# power_distributor.net
KiCad netlist of a schematic drawn in EAGLE
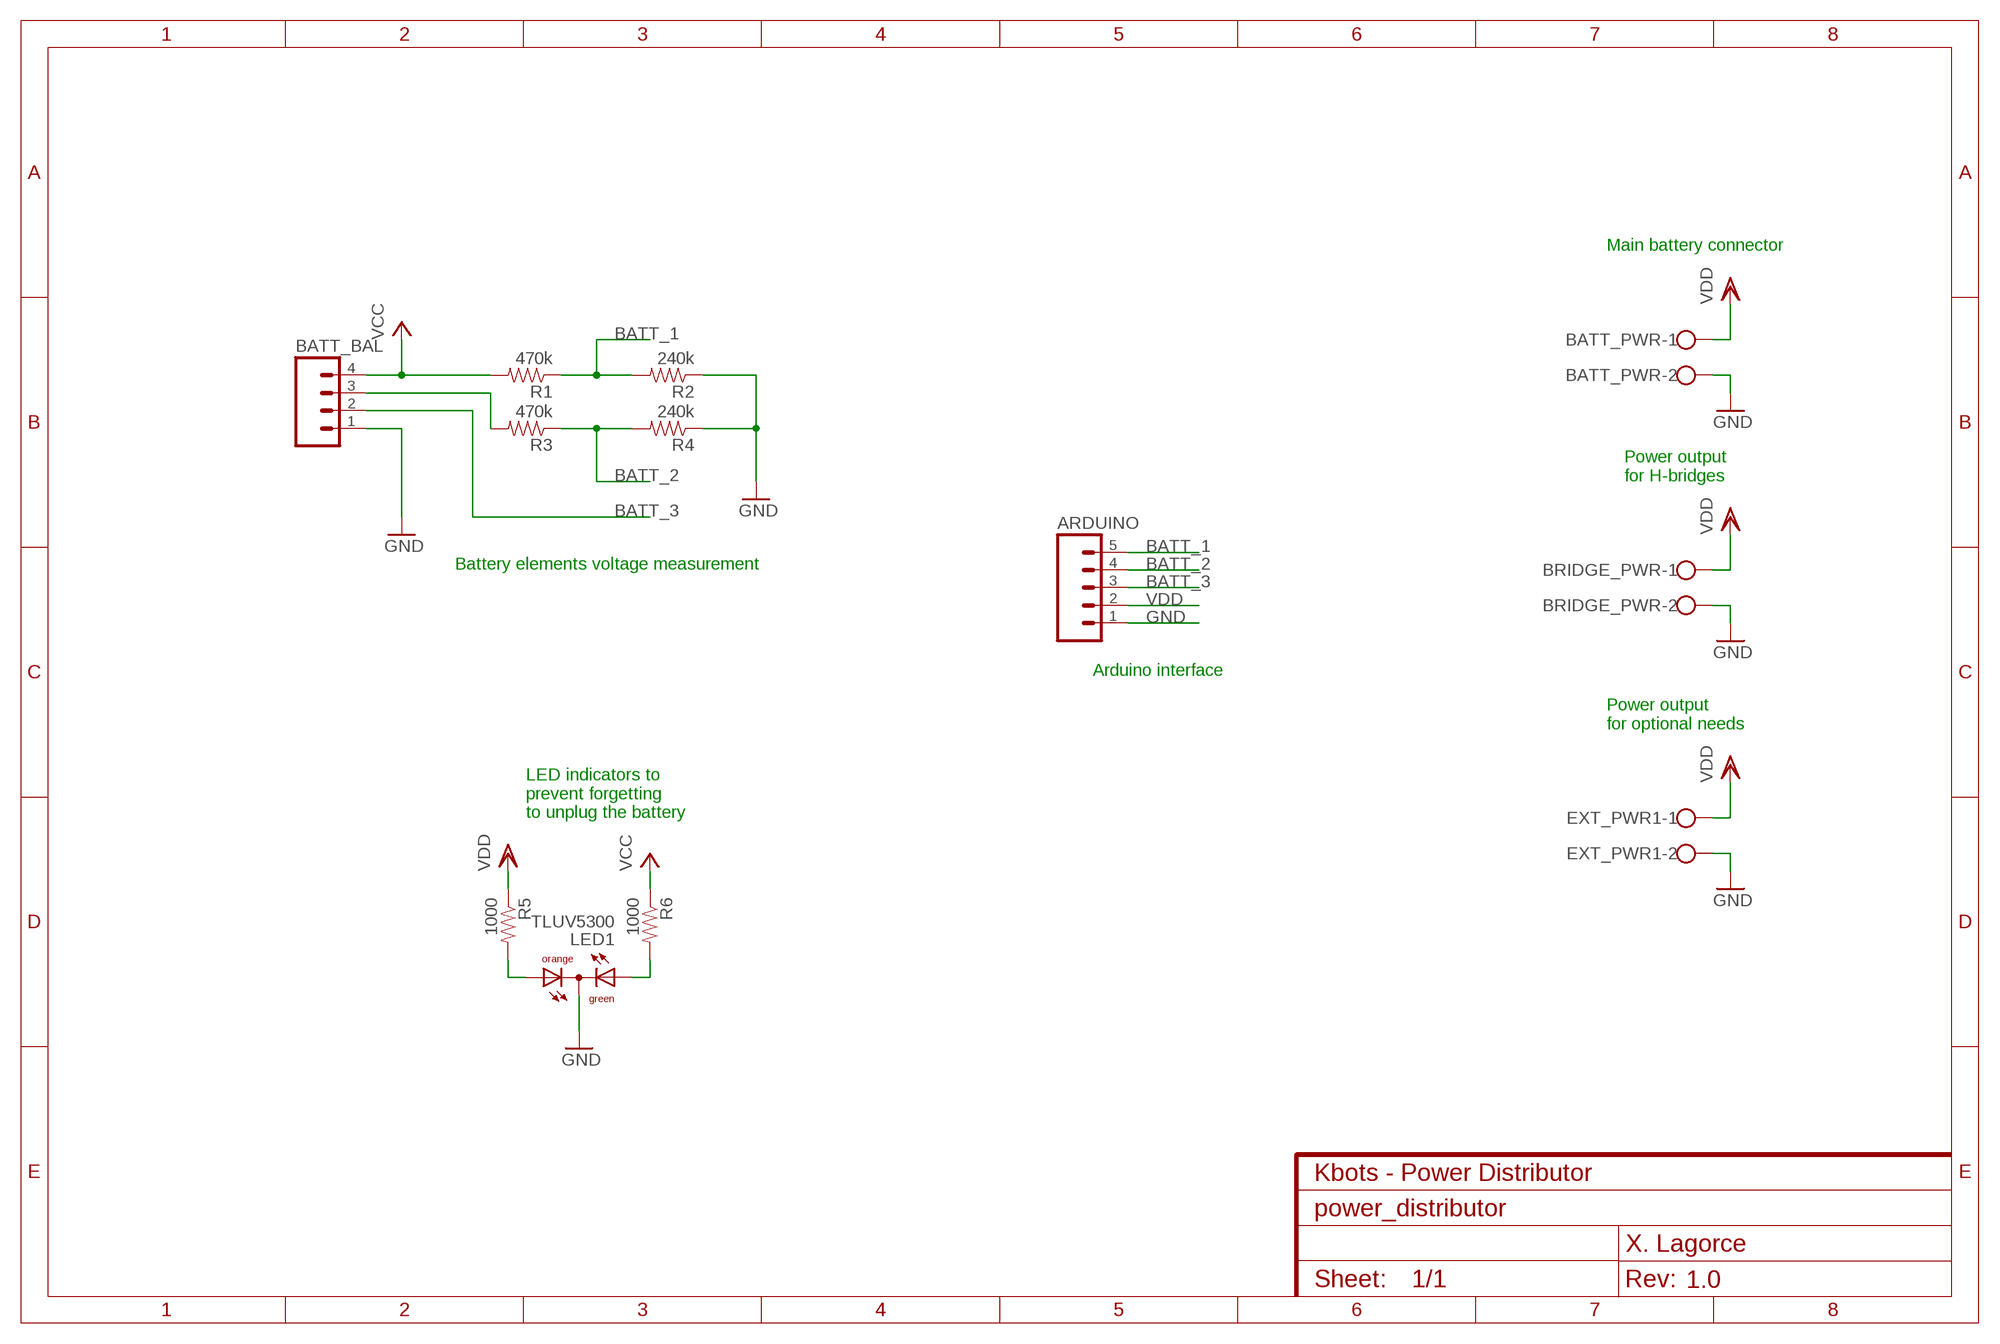
[diagram p0: schematic, sheet 1]

(export (version "E")
  (design (tool "Eeschema 10.0.6"))
  (components
    (comp (ref "ARDUINO")
      (value "M05PTH")
      (footprint "eagle-import:1X05")
      (libsource (lib "eagle-import") (part "M05PTH"))
    )
    (comp (ref "BATT_BAL")
      (value "M04POLAR")
      (footprint "eagle-import:MOLEX-1X4")
      (libsource (lib "eagle-import") (part "M04POLAR"))
    )
    (comp (ref "BATT_PWR")
      (value "W237-102")
      (footprint "eagle-import:W237-102")
      (fields (field (name "MPN") "237-102"))
      (libsource (lib "eagle-import") (part "W237-102"))
    )
    (comp (ref "BRIDGE_PWR")
      (value "W237-102")
      (footprint "eagle-import:W237-102")
      (fields (field (name "MPN") "237-102"))
      (libsource (lib "eagle-import") (part "W237-102"))
    )
    (comp (ref "EXT_PWR1")
      (value "W237-102")
      (footprint "eagle-import:W237-102")
      (fields (field (name "MPN") "237-102"))
      (libsource (lib "eagle-import") (part "W237-102"))
    )
    (comp (ref "LED1")
      (value "TLUV5300")
      (footprint "eagle-import:TLUV5300")
      (libsource (lib "eagle-import") (part "TLUV5300"))
    )
    (comp (ref "R1")
      (value "470k")
      (footprint "eagle-import:1206")
      (libsource (lib "eagle-import") (part "RESISTOR1206"))
    )
    (comp (ref "R2")
      (value "240k")
      (footprint "eagle-import:1206")
      (libsource (lib "eagle-import") (part "RESISTOR1206"))
    )
    (comp (ref "R3")
      (value "470k")
      (footprint "eagle-import:1206")
      (libsource (lib "eagle-import") (part "RESISTOR1206"))
    )
    (comp (ref "R4")
      (value "240k")
      (footprint "eagle-import:1206")
      (libsource (lib "eagle-import") (part "RESISTOR1206"))
    )
    (comp (ref "R5")
      (value "1000")
      (footprint "eagle-import:1206")
      (libsource (lib "eagle-import") (part "RESISTOR1206"))
    )
    (comp (ref "R6")
      (value "1000")
      (footprint "eagle-import:1206")
      (libsource (lib "eagle-import") (part "RESISTOR1206"))
    )
  )
  (nets
    (net (code "1") (name "/BATT_1") (class "Default")
      (node (ref "ARDUINO") (pin "5") (pinfunction "5_5") (pintype "passive"))
      (node (ref "R1") (pin "1") (pinfunction "1_1") (pintype "passive"))
      (node (ref "R2") (pin "2") (pinfunction "2_2") (pintype "passive"))
    )
    (net (code "2") (name "/BATT_2") (class "Default")
      (node (ref "ARDUINO") (pin "4") (pinfunction "4_4") (pintype "passive"))
      (node (ref "R3") (pin "1") (pinfunction "1_1") (pintype "passive"))
      (node (ref "R4") (pin "2") (pinfunction "2_2") (pintype "passive"))
    )
    (net (code "3") (name "/BATT_3") (class "Default")
      (node (ref "ARDUINO") (pin "3") (pinfunction "3_3") (pintype "passive"))
      (node (ref "BATT_BAL") (pin "2") (pinfunction "2_2") (pintype "passive"))
    )
    (net (code "4") (name "GND") (class "Default")
      (node (ref "ARDUINO") (pin "1") (pinfunction "1_1") (pintype "passive"))
      (node (ref "BATT_BAL") (pin "1") (pinfunction "1_1") (pintype "passive"))
      (node (ref "BATT_PWR") (pin "2") (pinfunction "KL_2") (pintype "passive"))
      (node (ref "BRIDGE_PWR") (pin "2") (pinfunction "KL_2") (pintype "passive"))
      (node (ref "EXT_PWR1") (pin "2") (pinfunction "KL_2") (pintype "passive"))
      (node (ref "LED1") (pin "CC") (pinfunction "CC_CC") (pintype "passive"))
      (node (ref "R2") (pin "1") (pinfunction "1_1") (pintype "passive"))
      (node (ref "R4") (pin "1") (pinfunction "1_1") (pintype "passive"))
    )
    (net (code "5") (name "Net-(BATT_BAL-Pad3)") (class "Default")
      (node (ref "BATT_BAL") (pin "3") (pinfunction "3_3") (pintype "passive"))
      (node (ref "R3") (pin "2") (pinfunction "2_2") (pintype "passive"))
    )
    (net (code "6") (name "Net-(LED1-PadAG)") (class "Default")
      (node (ref "LED1") (pin "AG") (pinfunction "AG_AG") (pintype "passive"))
      (node (ref "R6") (pin "2") (pinfunction "2_2") (pintype "passive"))
    )
    (net (code "7") (name "Net-(LED1-PadAO)") (class "Default")
      (node (ref "LED1") (pin "AO") (pinfunction "AO_AO") (pintype "passive"))
      (node (ref "R5") (pin "2") (pinfunction "2_2") (pintype "passive"))
    )
    (net (code "8") (name "VCC") (class "Default")
      (node (ref "BATT_BAL") (pin "4") (pinfunction "4_4") (pintype "passive"))
      (node (ref "R1") (pin "2") (pinfunction "2_2") (pintype "passive"))
      (node (ref "R6") (pin "1") (pinfunction "1_1") (pintype "passive"))
    )
    (net (code "9") (name "VDD") (class "Default")
      (node (ref "ARDUINO") (pin "2") (pinfunction "2_2") (pintype "passive"))
      (node (ref "BATT_PWR") (pin "1") (pinfunction "KL_1") (pintype "passive"))
      (node (ref "BRIDGE_PWR") (pin "1") (pinfunction "KL_1") (pintype "passive"))
      (node (ref "EXT_PWR1") (pin "1") (pinfunction "KL_1") (pintype "passive"))
      (node (ref "R5") (pin "1") (pinfunction "1_1") (pintype "passive"))
    )
  )
)
